# Sensors_and_IO.net
KiCad netlist of a schematic drawn in Altium Designer
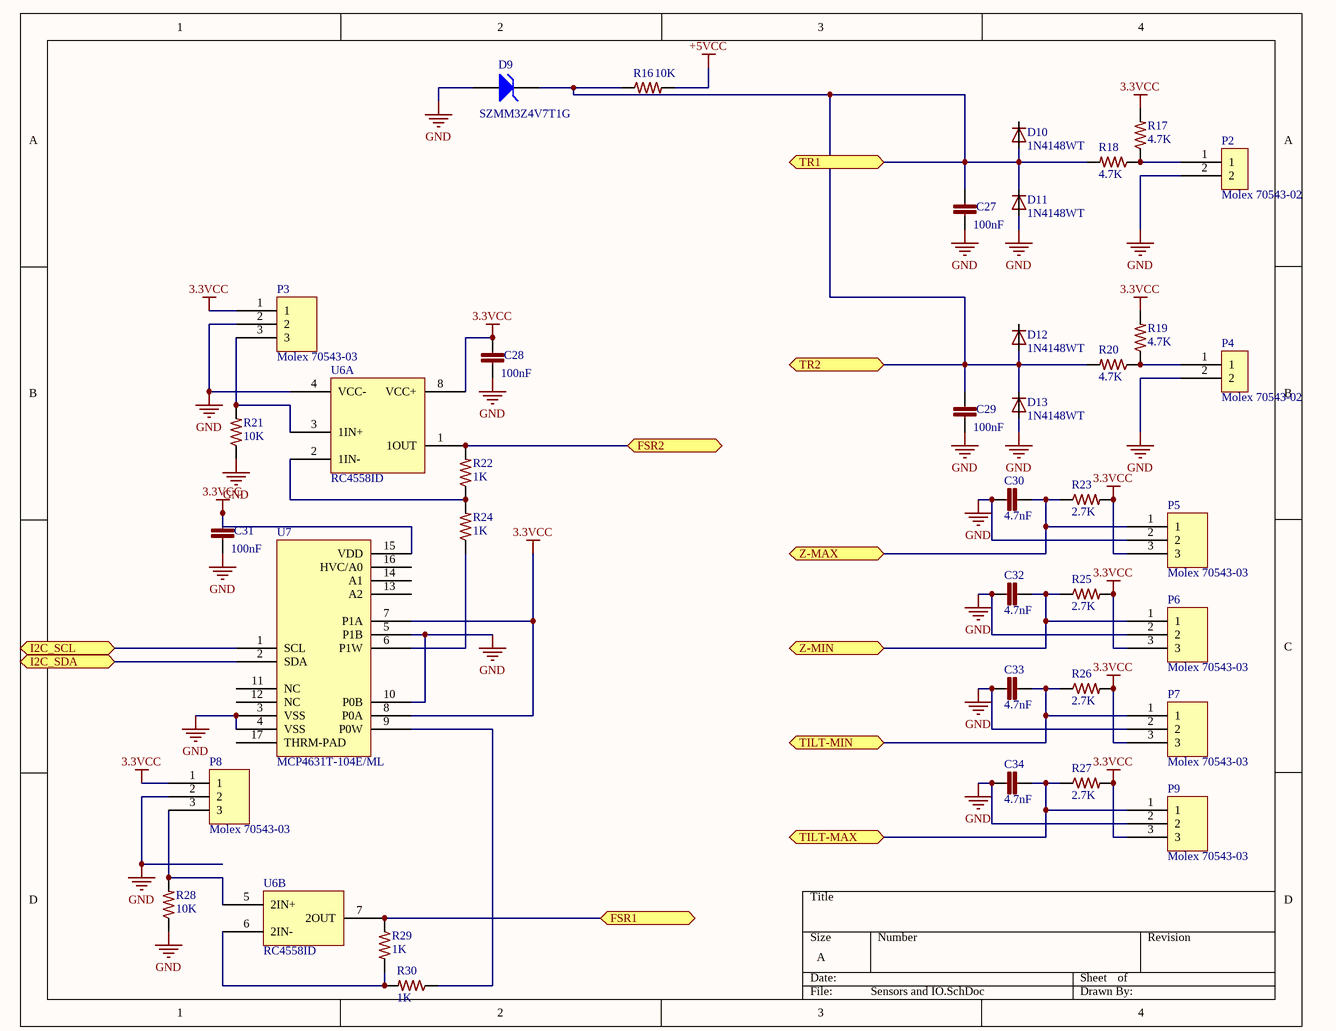
[diagram p0: Sensors and IO.SchDoc]

(export (version "E")
  (design (tool "Eeschema 10.0.6"))
  (components
    (comp (ref "C27")
      (value "100nF")
      (footprint "C0402")
      (description "CAP CER 0402 100nF 16V 10% X7R")
      (fields
        (field (name "MANUFACTURERPARTNUMBER") "GRM155R71C104KA88D")
        (field (name "PUBLISHER") "UltiMachine")
      )
      (libsource (lib "3Delight") (part "GRM155R71C104KA88D"))
    )
    (comp (ref "C28")
      (value "100nF")
      (footprint "C0402")
      (description "CAP CER 0402 100nF 16V 10% X7R")
      (fields
        (field (name "MANUFACTURERPARTNUMBER") "GRM155R71C104KA88D")
        (field (name "PUBLISHER") "UltiMachine")
      )
      (libsource (lib "3Delight") (part "GRM155R71C104KA88D"))
    )
    (comp (ref "C29")
      (value "100nF")
      (footprint "C0402")
      (description "CAP CER 0402 100nF 16V 10% X7R")
      (fields
        (field (name "MANUFACTURERPARTNUMBER") "GRM155R71C104KA88D")
        (field (name "PUBLISHER") "UltiMachine")
      )
      (libsource (lib "3Delight") (part "GRM155R71C104KA88D"))
    )
    (comp (ref "C30")
      (value "4.7nF")
      (footprint "C0402")
      (description "CAP CER 0402 4.7nF 25V 10% X7R")
      (fields
        (field (name "MANUFACTURERPARTNUMBER") "CC0402KRX7R8BB472")
        (field (name "PUBLISHER") "UltiMachine")
      )
      (libsource (lib "3Delight") (part "CC0402KRX7R8BB472"))
    )
    (comp (ref "C31")
      (value "100nF")
      (footprint "C0402")
      (description "CAP CER 0402 100nF 16V 10% X7R")
      (fields
        (field (name "MANUFACTURERPARTNUMBER") "GRM155R71C104KA88D")
        (field (name "PUBLISHER") "UltiMachine")
      )
      (libsource (lib "3Delight") (part "GRM155R71C104KA88D"))
    )
    (comp (ref "C32")
      (value "4.7nF")
      (footprint "C0402")
      (description "CAP CER 0402 4.7nF 25V 10% X7R")
      (fields
        (field (name "MANUFACTURERPARTNUMBER") "CC0402KRX7R8BB472")
        (field (name "PUBLISHER") "UltiMachine")
      )
      (libsource (lib "3Delight") (part "CC0402KRX7R8BB472"))
    )
    (comp (ref "C33")
      (value "4.7nF")
      (footprint "C0402")
      (description "CAP CER 0402 4.7nF 25V 10% X7R")
      (fields
        (field (name "MANUFACTURERPARTNUMBER") "CC0402KRX7R8BB472")
        (field (name "PUBLISHER") "UltiMachine")
      )
      (libsource (lib "3Delight") (part "CC0402KRX7R8BB472"))
    )
    (comp (ref "C34")
      (value "4.7nF")
      (footprint "C0402")
      (description "CAP CER 0402 4.7nF 25V 10% X7R")
      (fields
        (field (name "MANUFACTURERPARTNUMBER") "CC0402KRX7R8BB472")
        (field (name "PUBLISHER") "UltiMachine")
      )
      (libsource (lib "3Delight") (part "CC0402KRX7R8BB472"))
    )
    (comp (ref "D9")
      (value "SZMM3Z4V7T1G")
      (footprint "SZMM3Z4V7T1G")
      (description "Zener Diode")
      (fields (field (name "PUBLISHER") "Altium Limited"))
      (libsource (lib "Miscellaneous Devices") (part "D Zener"))
    )
    (comp (ref "D10")
      (value "1N4148WT")
      (footprint "SOD523")
      (description "DIODE SOD523")
      (fields (field (name "PUBLISHER") "UltiMachine"))
      (libsource (lib "3Delight") (part "1N4148WT"))
    )
    (comp (ref "D11")
      (value "1N4148WT")
      (footprint "SOD523")
      (description "DIODE SOD523")
      (fields (field (name "PUBLISHER") "UltiMachine"))
      (libsource (lib "3Delight") (part "1N4148WT"))
    )
    (comp (ref "D12")
      (value "1N4148WT")
      (footprint "SOD523")
      (description "DIODE SOD523")
      (fields (field (name "PUBLISHER") "UltiMachine"))
      (libsource (lib "3Delight") (part "1N4148WT"))
    )
    (comp (ref "D13")
      (value "1N4148WT")
      (footprint "SOD523")
      (description "DIODE SOD523")
      (fields (field (name "PUBLISHER") "UltiMachine"))
      (libsource (lib "3Delight") (part "1N4148WT"))
    )
    (comp (ref "P2")
      (value "Molex 70543-02")
      (footprint "70543-02")
      (libsource (lib "ZMBo Schematic Library") (part "Molex 70543-02"))
    )
    (comp (ref "P3")
      (value "Molex 70543-03")
      (footprint "70543-03")
      (libsource (lib "RADMBo Schematic Library") (part "Molex Endstop"))
    )
    (comp (ref "P4")
      (value "Molex 70543-02")
      (footprint "70543-02")
      (libsource (lib "ZMBo Schematic Library") (part "Molex 70543-02"))
    )
    (comp (ref "P5")
      (value "Molex 70543-03")
      (footprint "70543-03")
      (libsource (lib "RADMBo Schematic Library") (part "Molex Endstop"))
    )
    (comp (ref "P6")
      (value "Molex 70543-03")
      (footprint "70543-03")
      (libsource (lib "RADMBo Schematic Library") (part "Molex Endstop"))
    )
    (comp (ref "P7")
      (value "Molex 70543-03")
      (footprint "70543-03")
      (libsource (lib "RADMBo Schematic Library") (part "Molex Endstop"))
    )
    (comp (ref "P8")
      (value "Molex 70543-03")
      (footprint "70543-03")
      (libsource (lib "RADMBo Schematic Library") (part "Molex Endstop"))
    )
    (comp (ref "P9")
      (value "Molex 70543-03")
      (footprint "70543-03")
      (libsource (lib "RADMBo Schematic Library") (part "Molex Endstop"))
    )
    (comp (ref "R16")
      (value "10K")
      (footprint "R0603")
      (description "RES 0603 10K 100mW 1%")
      (fields
        (field (name "MANUFACTURERPARTNUMBER") "ERJ-3EKF1002V")
        (field (name "PUBLISHER") "UltiMachine")
      )
      (libsource (lib "3Delight") (part "ERJ-3EKF1002V"))
    )
    (comp (ref "R17")
      (value "4.7K")
      (footprint "R0603")
      (description "RES 0603 4.7K 100mW 1%")
      (fields (field (name "MANUFACTURERPARTNUMBER") "ERJ3EKF4701V") (field (name "PUBLISHER") "UltiMachine"))
      (libsource (lib "3Delight") (part "ERJ3EKF4701V"))
    )
    (comp (ref "R18")
      (value "4.7K")
      (footprint "R0603")
      (description "RES 0603 4.7K 100mW 1%")
      (fields (field (name "MANUFACTURERPARTNUMBER") "ERJ3EKF4701V") (field (name "PUBLISHER") "UltiMachine"))
      (libsource (lib "3Delight") (part "ERJ3EKF4701V"))
    )
    (comp (ref "R19")
      (value "4.7K")
      (footprint "R0603")
      (description "RES 0603 4.7K 100mW 1%")
      (fields (field (name "MANUFACTURERPARTNUMBER") "ERJ3EKF4701V") (field (name "PUBLISHER") "UltiMachine"))
      (libsource (lib "3Delight") (part "ERJ3EKF4701V"))
    )
    (comp (ref "R20")
      (value "4.7K")
      (footprint "R0603")
      (description "RES 0603 4.7K 100mW 1%")
      (fields (field (name "MANUFACTURERPARTNUMBER") "ERJ3EKF4701V") (field (name "PUBLISHER") "UltiMachine"))
      (libsource (lib "3Delight") (part "ERJ3EKF4701V"))
    )
    (comp (ref "R21")
      (value "10K")
      (footprint "R0603")
      (description "RES 0603 10K 100mW 1%")
      (fields
        (field (name "MANUFACTURERPARTNUMBER") "ERJ-3EKF1002V")
        (field (name "PUBLISHER") "UltiMachine")
      )
      (libsource (lib "3Delight") (part "ERJ-3EKF1002V"))
    )
    (comp (ref "R22")
      (value "1K")
      (footprint "R0603")
      (description "RES 0603 1K 100mW 1%")
      (fields
        (field (name "MANUFACTURERPARTNUMBER") "ERJ-3EKF1001V")
        (field (name "PUBLISHER") "UltiMachine")
      )
      (libsource (lib "3Delight") (part "ERJ-3EKF1001V"))
    )
    (comp (ref "R23")
      (value "2.7K")
      (footprint "R0402")
      (description "RES SMD 2.7K OHM 5% 1/10W 0402")
      (fields
        (field (name "MANUFACTURERPARTNUMBER") "ERJ-2GEJ272X")
        (field (name "TOLERANCE") "5%")
        (field (name "PUBLISHER") "Adam Vadala-Roth")
      )
      (libsource (lib "Tigershark3D") (part "ERJ-2GEJ272X"))
    )
    (comp (ref "R24")
      (value "1K")
      (footprint "R0603")
      (description "RES 0603 1K 100mW 1%")
      (fields
        (field (name "MANUFACTURERPARTNUMBER") "ERJ-3EKF1001V")
        (field (name "PUBLISHER") "UltiMachine")
      )
      (libsource (lib "3Delight") (part "ERJ-3EKF1001V"))
    )
    (comp (ref "R25")
      (value "2.7K")
      (footprint "R0402")
      (description "RES SMD 2.7K OHM 5% 1/10W 0402")
      (fields
        (field (name "MANUFACTURERPARTNUMBER") "ERJ-2GEJ272X")
        (field (name "TOLERANCE") "5%")
        (field (name "PUBLISHER") "Adam Vadala-Roth")
      )
      (libsource (lib "Tigershark3D") (part "ERJ-2GEJ272X"))
    )
    (comp (ref "R26")
      (value "2.7K")
      (footprint "R0402")
      (description "RES SMD 2.7K OHM 5% 1/10W 0402")
      (fields
        (field (name "MANUFACTURERPARTNUMBER") "ERJ-2GEJ272X")
        (field (name "TOLERANCE") "5%")
        (field (name "PUBLISHER") "Adam Vadala-Roth")
      )
      (libsource (lib "Tigershark3D") (part "ERJ-2GEJ272X"))
    )
    (comp (ref "R27")
      (value "2.7K")
      (footprint "R0402")
      (description "RES SMD 2.7K OHM 5% 1/10W 0402")
      (fields
        (field (name "MANUFACTURERPARTNUMBER") "ERJ-2GEJ272X")
        (field (name "TOLERANCE") "5%")
        (field (name "PUBLISHER") "Adam Vadala-Roth")
      )
      (libsource (lib "Tigershark3D") (part "ERJ-2GEJ272X"))
    )
    (comp (ref "R28")
      (value "10K")
      (footprint "R0603")
      (description "RES 0603 10K 100mW 1%")
      (fields
        (field (name "MANUFACTURERPARTNUMBER") "ERJ-3EKF1002V")
        (field (name "PUBLISHER") "UltiMachine")
      )
      (libsource (lib "3Delight") (part "ERJ-3EKF1002V"))
    )
    (comp (ref "R29")
      (value "1K")
      (footprint "R0603")
      (description "RES 0603 1K 100mW 1%")
      (fields
        (field (name "MANUFACTURERPARTNUMBER") "ERJ-3EKF1001V")
        (field (name "PUBLISHER") "UltiMachine")
      )
      (libsource (lib "3Delight") (part "ERJ-3EKF1001V"))
    )
    (comp (ref "R30")
      (value "1K")
      (footprint "R0603")
      (description "RES 0603 1K 100mW 1%")
      (fields
        (field (name "MANUFACTURERPARTNUMBER") "ERJ-3EKF1001V")
        (field (name "PUBLISHER") "UltiMachine")
      )
      (libsource (lib "3Delight") (part "ERJ-3EKF1001V"))
    )
    (comp (ref "U6")
      (value "RC4558ID")
      (footprint "TSOP65P490X110-8N")
      (fields (field (name "MFR") "Ti"))
      (libsource (lib "") (part "RC4558ID_1"))
    )
    (comp (ref "U7")
      (value "MCP4631T-104E/ML")
      (footprint "MCP4631T-104E/ML")
      (description "IC DGTL POT 100K 129TAPS 16-QF")
      (fields (field (name "MFR") "Microchip"))
      (libsource (lib "GenesysHat") (part "MCP4631T-104E/ML"))
    )
  )
  (nets
    (net (code "1") (name "+5VCC") (class "Default")
      (node (ref "R16") (pin "2") (pinfunction "2_2") (pintype "passive"))
    )
    (net (code "2") (name "/FSR1") (class "Default")
      (node (ref "R29") (pin "1") (pinfunction "1_1") (pintype "passive"))
      (node (ref "U6") (pin "7") (pinfunction "2OUT_7") (pintype "passive"))
    )
    (net (code "3") (name "/FSR2") (class "Default")
      (node (ref "R22") (pin "2") (pinfunction "2_2") (pintype "passive"))
      (node (ref "U6") (pin "1") (pinfunction "1OUT_1") (pintype "passive"))
    )
    (net (code "4") (name "/I2C_SCL") (class "Default")
      (node (ref "U7") (pin "1") (pinfunction "SCL_1") (pintype "passive"))
    )
    (net (code "5") (name "/I2C_SDA") (class "Default")
      (node (ref "U7") (pin "2") (pinfunction "SDA_2") (pintype "passive"))
    )
    (net (code "6") (name "/TILT-MAX") (class "Default")
      (node (ref "C34") (pin "2") (pinfunction "2_2") (pintype "passive"))
      (node (ref "P9") (pin "1") (pinfunction "1_1") (pintype "passive"))
      (node (ref "R27") (pin "1") (pinfunction "1_1") (pintype "passive"))
    )
    (net (code "7") (name "/TILT-MIN") (class "Default")
      (node (ref "C33") (pin "2") (pinfunction "2_2") (pintype "passive"))
      (node (ref "P7") (pin "1") (pinfunction "1_1") (pintype "passive"))
      (node (ref "R26") (pin "1") (pinfunction "1_1") (pintype "passive"))
    )
    (net (code "8") (name "/TR1") (class "Default")
      (node (ref "C27") (pin "1") (pinfunction "1_1") (pintype "passive"))
      (node (ref "C29") (pin "1") (pinfunction "1_1") (pintype "passive"))
      (node (ref "D10") (pin "A") (pinfunction "A_A") (pintype "passive"))
      (node (ref "D11") (pin "C") (pinfunction "C_C") (pintype "passive"))
      (node (ref "D12") (pin "A") (pinfunction "A_A") (pintype "passive"))
      (node (ref "D13") (pin "C") (pinfunction "C_C") (pintype "passive"))
      (node (ref "D9") (pin "2") (pinfunction "K_2") (pintype "passive"))
      (node (ref "R16") (pin "1") (pinfunction "1_1") (pintype "passive"))
      (node (ref "R18") (pin "2") (pinfunction "2_2") (pintype "passive"))
      (node (ref "R20") (pin "2") (pinfunction "2_2") (pintype "passive"))
    )
    (net (code "9") (name "/Z-MAX") (class "Default")
      (node (ref "C30") (pin "2") (pinfunction "2_2") (pintype "passive"))
      (node (ref "P5") (pin "1") (pinfunction "1_1") (pintype "passive"))
      (node (ref "R23") (pin "1") (pinfunction "1_1") (pintype "passive"))
    )
    (net (code "10") (name "/Z-MIN") (class "Default")
      (node (ref "C32") (pin "2") (pinfunction "2_2") (pintype "passive"))
      (node (ref "P6") (pin "1") (pinfunction "1_1") (pintype "passive"))
      (node (ref "R25") (pin "1") (pinfunction "1_1") (pintype "passive"))
    )
    (net (code "11") (name "3.3VCC") (class "Default")
      (node (ref "C28") (pin "1") (pinfunction "1_1") (pintype "passive"))
      (node (ref "C31") (pin "1") (pinfunction "1_1") (pintype "passive"))
      (node (ref "P3") (pin "1") (pinfunction "1_1") (pintype "passive"))
      (node (ref "P5") (pin "3") (pinfunction "3_3") (pintype "passive"))
      (node (ref "P6") (pin "3") (pinfunction "3_3") (pintype "passive"))
      (node (ref "P7") (pin "3") (pinfunction "3_3") (pintype "passive"))
      (node (ref "P8") (pin "1") (pinfunction "1_1") (pintype "passive"))
      (node (ref "P9") (pin "3") (pinfunction "3_3") (pintype "passive"))
      (node (ref "R17") (pin "2") (pinfunction "2_2") (pintype "passive"))
      (node (ref "R19") (pin "2") (pinfunction "2_2") (pintype "passive"))
      (node (ref "R23") (pin "2") (pinfunction "2_2") (pintype "passive"))
      (node (ref "R25") (pin "2") (pinfunction "2_2") (pintype "passive"))
      (node (ref "R26") (pin "2") (pinfunction "2_2") (pintype "passive"))
      (node (ref "R27") (pin "2") (pinfunction "2_2") (pintype "passive"))
      (node (ref "U6") (pin "8") (pinfunction "VCC+_8") (pintype "passive"))
      (node (ref "U7") (pin "15") (pinfunction "VDD_15") (pintype "passive"))
      (node (ref "U7") (pin "7") (pinfunction "P1A_7") (pintype "passive"))
      (node (ref "U7") (pin "8") (pinfunction "P0A_8") (pintype "passive"))
    )
    (net (code "12") (name "GND") (class "Default")
      (node (ref "C27") (pin "2") (pinfunction "2_2") (pintype "passive"))
      (node (ref "C28") (pin "2") (pinfunction "2_2") (pintype "passive"))
      (node (ref "C29") (pin "2") (pinfunction "2_2") (pintype "passive"))
      (node (ref "C30") (pin "1") (pinfunction "1_1") (pintype "passive"))
      (node (ref "C31") (pin "2") (pinfunction "2_2") (pintype "passive"))
      (node (ref "C32") (pin "1") (pinfunction "1_1") (pintype "passive"))
      (node (ref "C33") (pin "1") (pinfunction "1_1") (pintype "passive"))
      (node (ref "C34") (pin "1") (pinfunction "1_1") (pintype "passive"))
      (node (ref "D11") (pin "A") (pinfunction "A_A") (pintype "passive"))
      (node (ref "D13") (pin "A") (pinfunction "A_A") (pintype "passive"))
      (node (ref "D9") (pin "1") (pinfunction "A_1") (pintype "passive"))
      (node (ref "P2") (pin "2") (pinfunction "2_2") (pintype "passive"))
      (node (ref "P3") (pin "2") (pinfunction "2_2") (pintype "passive"))
      (node (ref "P4") (pin "2") (pinfunction "2_2") (pintype "passive"))
      (node (ref "P5") (pin "2") (pinfunction "2_2") (pintype "passive"))
      (node (ref "P6") (pin "2") (pinfunction "2_2") (pintype "passive"))
      (node (ref "P7") (pin "2") (pinfunction "2_2") (pintype "passive"))
      (node (ref "P8") (pin "2") (pinfunction "2_2") (pintype "passive"))
      (node (ref "P9") (pin "2") (pinfunction "2_2") (pintype "passive"))
      (node (ref "R21") (pin "1") (pinfunction "1_1") (pintype "passive"))
      (node (ref "R28") (pin "1") (pinfunction "1_1") (pintype "passive"))
      (node (ref "U6") (pin "4") (pinfunction "VCC-_4") (pintype "passive"))
      (node (ref "U7") (pin "10") (pinfunction "P0B_10") (pintype "passive"))
      (node (ref "U7") (pin "3") (pinfunction "VSS_3") (pintype "passive"))
      (node (ref "U7") (pin "4") (pinfunction "VSS_4") (pintype "passive"))
      (node (ref "U7") (pin "5") (pinfunction "P1B_5") (pintype "passive"))
    )
    (net (code "13") (name "Net-(P2-Pad1)") (class "Default")
      (node (ref "P2") (pin "1") (pinfunction "1_1") (pintype "passive"))
      (node (ref "R17") (pin "1") (pinfunction "1_1") (pintype "passive"))
      (node (ref "R18") (pin "1") (pinfunction "1_1") (pintype "passive"))
    )
    (net (code "14") (name "Net-(P4-Pad1)") (class "Default")
      (node (ref "P4") (pin "1") (pinfunction "1_1") (pintype "passive"))
      (node (ref "R19") (pin "1") (pinfunction "1_1") (pintype "passive"))
      (node (ref "R20") (pin "1") (pinfunction "1_1") (pintype "passive"))
    )
    (net (code "15") (name "Net-(U6A-1IN+)") (class "Default")
      (node (ref "P3") (pin "3") (pinfunction "3_3") (pintype "passive"))
      (node (ref "R21") (pin "2") (pinfunction "2_2") (pintype "passive"))
      (node (ref "U6") (pin "3") (pinfunction "1IN+_3") (pintype "passive"))
    )
    (net (code "16") (name "Net-(U6A-1IN-)") (class "Default")
      (node (ref "R22") (pin "1") (pinfunction "1_1") (pintype "passive"))
      (node (ref "R24") (pin "2") (pinfunction "2_2") (pintype "passive"))
      (node (ref "U6") (pin "2") (pinfunction "1IN-_2") (pintype "passive"))
    )
    (net (code "17") (name "Net-(U6B-2IN+)") (class "Default")
      (node (ref "P8") (pin "3") (pinfunction "3_3") (pintype "passive"))
      (node (ref "R28") (pin "2") (pinfunction "2_2") (pintype "passive"))
      (node (ref "U6") (pin "5") (pinfunction "2IN+_5") (pintype "passive"))
    )
    (net (code "18") (name "Net-(U6B-2IN-)") (class "Default")
      (node (ref "R29") (pin "2") (pinfunction "2_2") (pintype "passive"))
      (node (ref "R30") (pin "2") (pinfunction "2_2") (pintype "passive"))
      (node (ref "U6") (pin "6") (pinfunction "2IN-_6") (pintype "passive"))
    )
    (net (code "19") (name "Net-(U7-P0W)") (class "Default")
      (node (ref "R30") (pin "1") (pinfunction "1_1") (pintype "passive"))
      (node (ref "U7") (pin "9") (pinfunction "P0W_9") (pintype "passive"))
    )
    (net (code "20") (name "Net-(U7-P1W)") (class "Default")
      (node (ref "R24") (pin "1") (pinfunction "1_1") (pintype "passive"))
      (node (ref "U7") (pin "6") (pinfunction "P1W_6") (pintype "passive"))
    )
    (net (code "21") (name "unconnected-(D10-PadC)") (class "Default")
      (node (ref "D10") (pin "C") (pinfunction "C_C") (pintype "passive"))
    )
    (net (code "22") (name "unconnected-(D12-PadC)") (class "Default")
      (node (ref "D12") (pin "C") (pinfunction "C_C") (pintype "passive"))
    )
    (net (code "23") (name "unconnected-(U7-A1-Pad14)") (class "Default")
      (node (ref "U7") (pin "14") (pinfunction "A1_14") (pintype "passive"))
    )
    (net (code "24") (name "unconnected-(U7-A2-Pad13)") (class "Default")
      (node (ref "U7") (pin "13") (pinfunction "A2_13") (pintype "passive"))
    )
    (net (code "25") (name "unconnected-(U7-HVC{slash}A0-Pad16)") (class "Default")
      (node (ref "U7") (pin "16") (pinfunction "HVC/A0_16") (pintype "passive"))
    )
    (net (code "26") (name "unconnected-(U7-NC-Pad11)") (class "Default")
      (node (ref "U7") (pin "11") (pinfunction "NC_11") (pintype "passive"))
    )
    (net (code "27") (name "unconnected-(U7-NC-Pad12)") (class "Default")
      (node (ref "U7") (pin "12") (pinfunction "NC_12") (pintype "passive"))
    )
    (net (code "28") (name "unconnected-(U7-THRM-PAD-Pad17)") (class "Default")
      (node (ref "U7") (pin "17") (pinfunction "THRM-PAD_17") (pintype "passive"))
    )
  )
)
